# rak833-hat.net
KiCad netlist of a schematic drawn in EAGLE
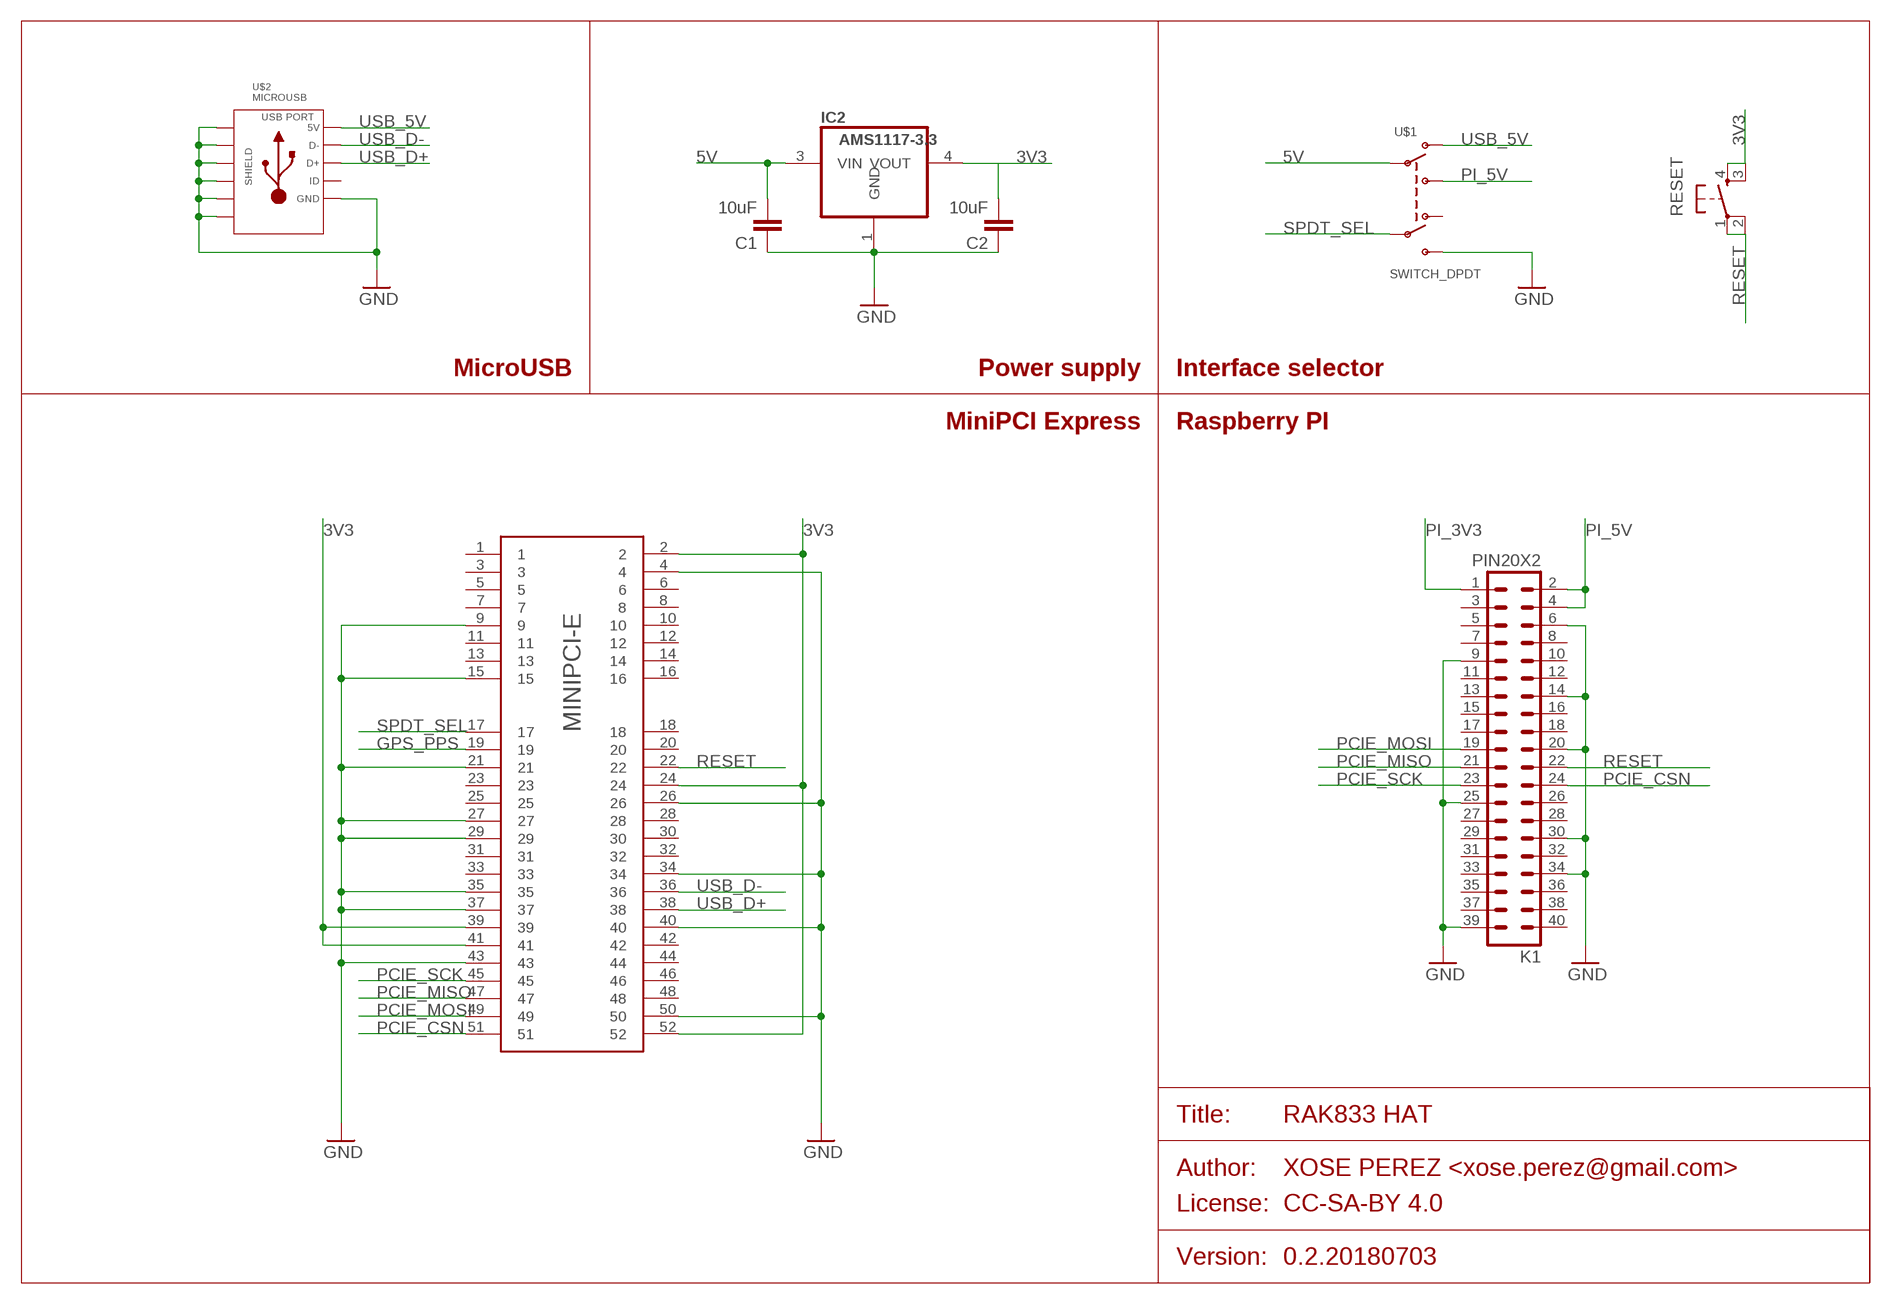
[diagram p0: schematic, sheet 1]

(export (version "E")
  (design (tool "Eeschema 10.0.6"))
  (components
    (comp (ref "C1")
      (value "10uF")
      (footprint "eagle-import:0805")
      (libsource (lib "eagle-import") (part "C-EU0805"))
    )
    (comp (ref "C2")
      (value "10uF")
      (footprint "eagle-import:0805")
      (libsource (lib "eagle-import") (part "C-EU0805"))
    )
    (comp (ref "IC2")
      (value "AMS1117-3.3")
      (footprint "eagle-import:SOT223")
      (libsource (lib "eagle-import") (part "REG1117SOT223-2"))
    )
    (comp (ref "K1")
      (value "PIN20X2")
      (footprint "eagle-import:PIN_20X2")
      (libsource (lib "eagle-import") (part "PIN20X2"))
    )
    (comp (ref "MINIPCI-E")
      (value "MINI-PCIE-RAW")
      (footprint "eagle-import:67910-MINI-PCIE")
      (libsource (lib "eagle-import") (part "MINI-PCIE-RAW"))
    )
    (comp (ref "RESET")
      (value "TACTILE_BUTTON_SMD")
      (footprint "eagle-import:TACTILE-BUTTON-SMD")
      (libsource (lib "eagle-import") (part "TACTILE_BUTTON_SMD"))
    )
    (comp (ref "U$1")
      (value "SWITCH_DPDT")
      (footprint "eagle-import:SWITCH_DPDT_SMD")
      (libsource (lib "eagle-import") (part "SWITCH_DPDT"))
    )
    (comp (ref "U$2")
      (value "MICROUSB")
      (footprint "eagle-import:MICROUSB-MOLEX-47346-0001")
      (libsource (lib "eagle-import") (part "MICROUSB"))
    )
  )
  (nets
    (net (code "1") (name "/3V3") (class "Default")
      (node (ref "C2") (pin "2") (pinfunction "2_2") (pintype "passive"))
      (node (ref "IC2") (pin "4") (pinfunction "VOUT_4") (pintype "output"))
      (node (ref "MINIPCI-E") (pin "2") (pinfunction "2_2") (pintype "bidirectional"))
      (node (ref "MINIPCI-E") (pin "24") (pinfunction "24_24") (pintype "bidirectional"))
      (node (ref "MINIPCI-E") (pin "39") (pinfunction "39_39") (pintype "bidirectional"))
      (node (ref "MINIPCI-E") (pin "41") (pinfunction "41_41") (pintype "bidirectional"))
      (node (ref "MINIPCI-E") (pin "52") (pinfunction "52_52") (pintype "bidirectional"))
      (node (ref "RESET") (pin "3") (pinfunction "SWB2_3") (pintype "passive"))
      (node (ref "RESET") (pin "4") (pinfunction "SWA2_4") (pintype "passive"))
    )
    (net (code "2") (name "/5V") (class "Default")
      (node (ref "C1") (pin "2") (pinfunction "2_2") (pintype "passive"))
      (node (ref "IC2") (pin "3") (pinfunction "VIN_3") (pintype "input"))
      (node (ref "U$1") (pin "A1") (pinfunction "P1_A1") (pintype "passive"))
    )
    (net (code "3") (name "/GPS_PPS") (class "Default")
      (node (ref "MINIPCI-E") (pin "19") (pinfunction "19_19") (pintype "bidirectional"))
    )
    (net (code "4") (name "/PCIE_CSN") (class "Default")
      (node (ref "K1") (pin "24") (pinfunction "24_24") (pintype "passive"))
      (node (ref "MINIPCI-E") (pin "51") (pinfunction "51_51") (pintype "bidirectional"))
    )
    (net (code "5") (name "/PCIE_MISO") (class "Default")
      (node (ref "K1") (pin "21") (pinfunction "21_21") (pintype "passive"))
      (node (ref "MINIPCI-E") (pin "47") (pinfunction "47_47") (pintype "bidirectional"))
    )
    (net (code "6") (name "/PCIE_MOSI") (class "Default")
      (node (ref "K1") (pin "19") (pinfunction "19_19") (pintype "passive"))
      (node (ref "MINIPCI-E") (pin "49") (pinfunction "49_49") (pintype "bidirectional"))
    )
    (net (code "7") (name "/PCIE_SCK") (class "Default")
      (node (ref "K1") (pin "23") (pinfunction "23_23") (pintype "passive"))
      (node (ref "MINIPCI-E") (pin "45") (pinfunction "45_45") (pintype "bidirectional"))
    )
    (net (code "8") (name "/PI_3V3") (class "Default")
      (node (ref "K1") (pin "1") (pinfunction "1_1") (pintype "passive"))
    )
    (net (code "9") (name "/PI_5V") (class "Default")
      (node (ref "K1") (pin "2") (pinfunction "2_2") (pintype "passive"))
      (node (ref "K1") (pin "4") (pinfunction "4_4") (pintype "passive"))
      (node (ref "U$1") (pin "C1") (pinfunction "S1_C1") (pintype "passive"))
    )
    (net (code "10") (name "/RESET") (class "Default")
      (node (ref "K1") (pin "22") (pinfunction "22_22") (pintype "passive"))
      (node (ref "MINIPCI-E") (pin "22") (pinfunction "22_22") (pintype "bidirectional"))
      (node (ref "RESET") (pin "1") (pinfunction "SWA1_1") (pintype "passive"))
      (node (ref "RESET") (pin "2") (pinfunction "SWB1_2") (pintype "passive"))
    )
    (net (code "11") (name "/SPDT_SEL") (class "Default")
      (node (ref "MINIPCI-E") (pin "17") (pinfunction "17_17") (pintype "bidirectional"))
      (node (ref "U$1") (pin "A2") (pinfunction "P2_A2") (pintype "passive"))
    )
    (net (code "12") (name "/USB_5V") (class "Default")
      (node (ref "U$1") (pin "B1") (pinfunction "O1_B1") (pintype "passive"))
      (node (ref "U$2") (pin "VCC") (pinfunction "5V_VCC") (pintype "power_in"))
    )
    (net (code "13") (name "/USB_D+") (class "Default")
      (node (ref "MINIPCI-E") (pin "38") (pinfunction "38_38") (pintype "bidirectional"))
      (node (ref "U$2") (pin "D+") (pinfunction "D+_D+") (pintype "bidirectional"))
    )
    (net (code "14") (name "/USB_D-") (class "Default")
      (node (ref "MINIPCI-E") (pin "36") (pinfunction "36_36") (pintype "bidirectional"))
      (node (ref "U$2") (pin "D-") (pinfunction "D-_D-") (pintype "bidirectional"))
    )
    (net (code "15") (name "GND") (class "Default")
      (node (ref "C1") (pin "1") (pinfunction "1_1") (pintype "passive"))
      (node (ref "C2") (pin "1") (pinfunction "1_1") (pintype "passive"))
      (node (ref "IC2") (pin "1") (pinfunction "GND_1") (pintype "power_in"))
      (node (ref "K1") (pin "14") (pinfunction "14_14") (pintype "passive"))
      (node (ref "K1") (pin "20") (pinfunction "20_20") (pintype "passive"))
      (node (ref "K1") (pin "25") (pinfunction "25_25") (pintype "passive"))
      (node (ref "K1") (pin "30") (pinfunction "30_30") (pintype "passive"))
      (node (ref "K1") (pin "34") (pinfunction "34_34") (pintype "passive"))
      (node (ref "K1") (pin "39") (pinfunction "39_39") (pintype "passive"))
      (node (ref "K1") (pin "6") (pinfunction "6_6") (pintype "passive"))
      (node (ref "K1") (pin "9") (pinfunction "9_9") (pintype "passive"))
      (node (ref "MINIPCI-E") (pin "15") (pinfunction "15_15") (pintype "bidirectional"))
      (node (ref "MINIPCI-E") (pin "21") (pinfunction "21_21") (pintype "bidirectional"))
      (node (ref "MINIPCI-E") (pin "26") (pinfunction "26_26") (pintype "bidirectional"))
      (node (ref "MINIPCI-E") (pin "27") (pinfunction "27_27") (pintype "bidirectional"))
      (node (ref "MINIPCI-E") (pin "29") (pinfunction "29_29") (pintype "bidirectional"))
      (node (ref "MINIPCI-E") (pin "34") (pinfunction "34_34") (pintype "bidirectional"))
      (node (ref "MINIPCI-E") (pin "35") (pinfunction "35_35") (pintype "bidirectional"))
      (node (ref "MINIPCI-E") (pin "37") (pinfunction "37_37") (pintype "bidirectional"))
      (node (ref "MINIPCI-E") (pin "4") (pinfunction "4_4") (pintype "bidirectional"))
      (node (ref "MINIPCI-E") (pin "40") (pinfunction "40_40") (pintype "bidirectional"))
      (node (ref "MINIPCI-E") (pin "43") (pinfunction "43_43") (pintype "bidirectional"))
      (node (ref "MINIPCI-E") (pin "50") (pinfunction "50_50") (pintype "bidirectional"))
      (node (ref "MINIPCI-E") (pin "9") (pinfunction "9_9") (pintype "bidirectional"))
      (node (ref "U$1") (pin "C2") (pinfunction "S2_C2") (pintype "passive"))
      (node (ref "U$2") (pin "GND") (pinfunction "GND_GND") (pintype "power_in"))
      (node (ref "U$2") (pin "SLD1") (pinfunction "SLD1_SLD1") (pintype "power_in"))
      (node (ref "U$2") (pin "SLD2") (pinfunction "SLD2_SLD2") (pintype "power_in"))
      (node (ref "U$2") (pin "SLD3") (pinfunction "SLD3_SLD3") (pintype "power_in"))
      (node (ref "U$2") (pin "SLD4") (pinfunction "SLD4_SLD4") (pintype "power_in"))
      (node (ref "U$2") (pin "SLD5") (pinfunction "SLD5_SLD5") (pintype "power_in"))
      (node (ref "U$2") (pin "SLD6") (pinfunction "SLD6_SLD6") (pintype "power_in"))
    )
    (net (code "16") (name "unconnected-(K1-Pad3)") (class "Default")
      (node (ref "K1") (pin "3") (pinfunction "3_3") (pintype "passive"))
    )
    (net (code "17") (name "unconnected-(K1-Pad5)") (class "Default")
      (node (ref "K1") (pin "5") (pinfunction "5_5") (pintype "passive"))
    )
    (net (code "18") (name "unconnected-(K1-Pad7)") (class "Default")
      (node (ref "K1") (pin "7") (pinfunction "7_7") (pintype "passive"))
    )
    (net (code "19") (name "unconnected-(K1-Pad8)") (class "Default")
      (node (ref "K1") (pin "8") (pinfunction "8_8") (pintype "passive"))
    )
    (net (code "20") (name "unconnected-(K1-Pad10)") (class "Default")
      (node (ref "K1") (pin "10") (pinfunction "10_10") (pintype "passive"))
    )
    (net (code "21") (name "unconnected-(K1-Pad11)") (class "Default")
      (node (ref "K1") (pin "11") (pinfunction "11_11") (pintype "passive"))
    )
    (net (code "22") (name "unconnected-(K1-Pad12)") (class "Default")
      (node (ref "K1") (pin "12") (pinfunction "12_12") (pintype "passive"))
    )
    (net (code "23") (name "unconnected-(K1-Pad13)") (class "Default")
      (node (ref "K1") (pin "13") (pinfunction "13_13") (pintype "passive"))
    )
    (net (code "24") (name "unconnected-(K1-Pad15)") (class "Default")
      (node (ref "K1") (pin "15") (pinfunction "15_15") (pintype "passive"))
    )
    (net (code "25") (name "unconnected-(K1-Pad16)") (class "Default")
      (node (ref "K1") (pin "16") (pinfunction "16_16") (pintype "passive"))
    )
    (net (code "26") (name "unconnected-(K1-Pad17)") (class "Default")
      (node (ref "K1") (pin "17") (pinfunction "17_17") (pintype "passive"))
    )
    (net (code "27") (name "unconnected-(K1-Pad18)") (class "Default")
      (node (ref "K1") (pin "18") (pinfunction "18_18") (pintype "passive"))
    )
    (net (code "28") (name "unconnected-(K1-Pad26)") (class "Default")
      (node (ref "K1") (pin "26") (pinfunction "26_26") (pintype "passive"))
    )
    (net (code "29") (name "unconnected-(K1-Pad27)") (class "Default")
      (node (ref "K1") (pin "27") (pinfunction "27_27") (pintype "passive"))
    )
    (net (code "30") (name "unconnected-(K1-Pad28)") (class "Default")
      (node (ref "K1") (pin "28") (pinfunction "28_28") (pintype "passive"))
    )
    (net (code "31") (name "unconnected-(K1-Pad29)") (class "Default")
      (node (ref "K1") (pin "29") (pinfunction "29_29") (pintype "passive"))
    )
    (net (code "32") (name "unconnected-(K1-Pad31)") (class "Default")
      (node (ref "K1") (pin "31") (pinfunction "31_31") (pintype "passive"))
    )
    (net (code "33") (name "unconnected-(K1-Pad32)") (class "Default")
      (node (ref "K1") (pin "32") (pinfunction "32_32") (pintype "passive"))
    )
    (net (code "34") (name "unconnected-(K1-Pad33)") (class "Default")
      (node (ref "K1") (pin "33") (pinfunction "33_33") (pintype "passive"))
    )
    (net (code "35") (name "unconnected-(K1-Pad35)") (class "Default")
      (node (ref "K1") (pin "35") (pinfunction "35_35") (pintype "passive"))
    )
    (net (code "36") (name "unconnected-(K1-Pad36)") (class "Default")
      (node (ref "K1") (pin "36") (pinfunction "36_36") (pintype "passive"))
    )
    (net (code "37") (name "unconnected-(K1-Pad37)") (class "Default")
      (node (ref "K1") (pin "37") (pinfunction "37_37") (pintype "passive"))
    )
    (net (code "38") (name "unconnected-(K1-Pad38)") (class "Default")
      (node (ref "K1") (pin "38") (pinfunction "38_38") (pintype "passive"))
    )
    (net (code "39") (name "unconnected-(K1-Pad40)") (class "Default")
      (node (ref "K1") (pin "40") (pinfunction "40_40") (pintype "passive"))
    )
    (net (code "40") (name "unconnected-(MINIPCI-E-Pad1)") (class "Default")
      (node (ref "MINIPCI-E") (pin "1") (pinfunction "1_1") (pintype "bidirectional"))
    )
    (net (code "41") (name "unconnected-(MINIPCI-E-Pad3)") (class "Default")
      (node (ref "MINIPCI-E") (pin "3") (pinfunction "3_3") (pintype "bidirectional"))
    )
    (net (code "42") (name "unconnected-(MINIPCI-E-Pad5)") (class "Default")
      (node (ref "MINIPCI-E") (pin "5") (pinfunction "5_5") (pintype "bidirectional"))
    )
    (net (code "43") (name "unconnected-(MINIPCI-E-Pad6)") (class "Default")
      (node (ref "MINIPCI-E") (pin "6") (pinfunction "6_6") (pintype "bidirectional"))
    )
    (net (code "44") (name "unconnected-(MINIPCI-E-Pad7)") (class "Default")
      (node (ref "MINIPCI-E") (pin "7") (pinfunction "7_7") (pintype "bidirectional"))
    )
    (net (code "45") (name "unconnected-(MINIPCI-E-Pad8)") (class "Default")
      (node (ref "MINIPCI-E") (pin "8") (pinfunction "8_8") (pintype "bidirectional"))
    )
    (net (code "46") (name "unconnected-(MINIPCI-E-Pad10)") (class "Default")
      (node (ref "MINIPCI-E") (pin "10") (pinfunction "10_10") (pintype "bidirectional"))
    )
    (net (code "47") (name "unconnected-(MINIPCI-E-Pad11)") (class "Default")
      (node (ref "MINIPCI-E") (pin "11") (pinfunction "11_11") (pintype "bidirectional"))
    )
    (net (code "48") (name "unconnected-(MINIPCI-E-Pad12)") (class "Default")
      (node (ref "MINIPCI-E") (pin "12") (pinfunction "12_12") (pintype "bidirectional"))
    )
    (net (code "49") (name "unconnected-(MINIPCI-E-Pad13)") (class "Default")
      (node (ref "MINIPCI-E") (pin "13") (pinfunction "13_13") (pintype "bidirectional"))
    )
    (net (code "50") (name "unconnected-(MINIPCI-E-Pad14)") (class "Default")
      (node (ref "MINIPCI-E") (pin "14") (pinfunction "14_14") (pintype "bidirectional"))
    )
    (net (code "51") (name "unconnected-(MINIPCI-E-Pad16)") (class "Default")
      (node (ref "MINIPCI-E") (pin "16") (pinfunction "16_16") (pintype "bidirectional"))
    )
    (net (code "52") (name "unconnected-(MINIPCI-E-Pad18)") (class "Default")
      (node (ref "MINIPCI-E") (pin "18") (pinfunction "18_18") (pintype "bidirectional"))
    )
    (net (code "53") (name "unconnected-(MINIPCI-E-Pad20)") (class "Default")
      (node (ref "MINIPCI-E") (pin "20") (pinfunction "20_20") (pintype "bidirectional"))
    )
    (net (code "54") (name "unconnected-(MINIPCI-E-Pad23)") (class "Default")
      (node (ref "MINIPCI-E") (pin "23") (pinfunction "23_23") (pintype "bidirectional"))
    )
    (net (code "55") (name "unconnected-(MINIPCI-E-Pad25)") (class "Default")
      (node (ref "MINIPCI-E") (pin "25") (pinfunction "25_25") (pintype "bidirectional"))
    )
    (net (code "56") (name "unconnected-(MINIPCI-E-Pad28)") (class "Default")
      (node (ref "MINIPCI-E") (pin "28") (pinfunction "28_28") (pintype "bidirectional"))
    )
    (net (code "57") (name "unconnected-(MINIPCI-E-Pad30)") (class "Default")
      (node (ref "MINIPCI-E") (pin "30") (pinfunction "30_30") (pintype "bidirectional"))
    )
    (net (code "58") (name "unconnected-(MINIPCI-E-Pad31)") (class "Default")
      (node (ref "MINIPCI-E") (pin "31") (pinfunction "31_31") (pintype "bidirectional"))
    )
    (net (code "59") (name "unconnected-(MINIPCI-E-Pad32)") (class "Default")
      (node (ref "MINIPCI-E") (pin "32") (pinfunction "32_32") (pintype "bidirectional"))
    )
    (net (code "60") (name "unconnected-(MINIPCI-E-Pad33)") (class "Default")
      (node (ref "MINIPCI-E") (pin "33") (pinfunction "33_33") (pintype "bidirectional"))
    )
    (net (code "61") (name "unconnected-(MINIPCI-E-Pad42)") (class "Default")
      (node (ref "MINIPCI-E") (pin "42") (pinfunction "42_42") (pintype "bidirectional"))
    )
    (net (code "62") (name "unconnected-(MINIPCI-E-Pad44)") (class "Default")
      (node (ref "MINIPCI-E") (pin "44") (pinfunction "44_44") (pintype "bidirectional"))
    )
    (net (code "63") (name "unconnected-(MINIPCI-E-Pad46)") (class "Default")
      (node (ref "MINIPCI-E") (pin "46") (pinfunction "46_46") (pintype "bidirectional"))
    )
    (net (code "64") (name "unconnected-(MINIPCI-E-Pad48)") (class "Default")
      (node (ref "MINIPCI-E") (pin "48") (pinfunction "48_48") (pintype "bidirectional"))
    )
    (net (code "65") (name "unconnected-(U$1-O2-PadB2)") (class "Default")
      (node (ref "U$1") (pin "B2") (pinfunction "O2_B2") (pintype "passive"))
    )
    (net (code "66") (name "unconnected-(U$2-PadID)") (class "Default")
      (node (ref "U$2") (pin "ID") (pinfunction "ID_ID") (pintype "bidirectional"))
    )
  )
)
